# MiCore_LCD.net
KiCad netlist of a schematic drawn in Altium Designer
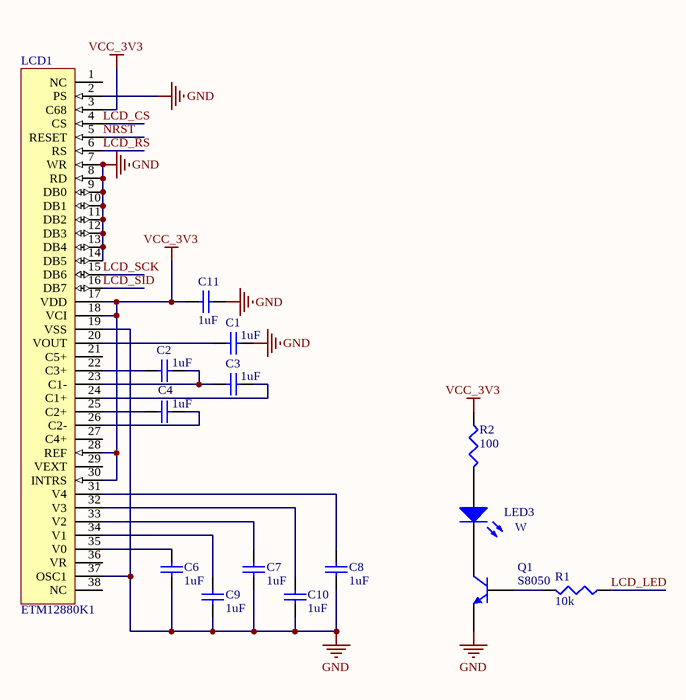
[diagram p0: MiCore_LCD.SchDoc]

(export (version "E")
  (design (tool "Eeschema 10.0.6"))
  (components
    (comp (ref "C1")
      (value "1uF")
      (footprint "0603C")
      (description "Capacitor")
      (fields (field (name "Comment") "Cap") (field (name "PUBLISHER") "Altium Limited"))
      (libsource (lib "Miscellaneous Devices") (part "Cap"))
    )
    (comp (ref "C2")
      (value "1uF")
      (footprint "0603C")
      (description "Capacitor")
      (fields (field (name "Comment") "Cap") (field (name "PUBLISHER") "Altium Limited"))
      (libsource (lib "Miscellaneous Devices") (part "Cap"))
    )
    (comp (ref "C3")
      (value "1uF")
      (footprint "0603C")
      (description "Capacitor")
      (fields (field (name "Comment") "Cap") (field (name "PUBLISHER") "Altium Limited"))
      (libsource (lib "Miscellaneous Devices") (part "Cap"))
    )
    (comp (ref "C4")
      (value "1uF")
      (footprint "0603C")
      (description "Capacitor")
      (fields (field (name "Comment") "Cap") (field (name "PUBLISHER") "Altium Limited"))
      (libsource (lib "Miscellaneous Devices") (part "Cap"))
    )
    (comp (ref "C6")
      (value "1uF")
      (footprint "0603C")
      (description "Capacitor")
      (fields (field (name "Comment") "Cap") (field (name "PUBLISHER") "Altium Limited"))
      (libsource (lib "Miscellaneous Devices") (part "Cap"))
    )
    (comp (ref "C7")
      (value "1uF")
      (footprint "0603C")
      (description "Capacitor")
      (fields (field (name "Comment") "Cap") (field (name "PUBLISHER") "Altium Limited"))
      (libsource (lib "Miscellaneous Devices") (part "Cap"))
    )
    (comp (ref "C8")
      (value "1uF")
      (footprint "0603C")
      (description "Capacitor")
      (fields (field (name "Comment") "Cap") (field (name "PUBLISHER") "Altium Limited"))
      (libsource (lib "Miscellaneous Devices") (part "Cap"))
    )
    (comp (ref "C9")
      (value "1uF")
      (footprint "0603C")
      (description "Capacitor")
      (fields (field (name "Comment") "Cap") (field (name "PUBLISHER") "Altium Limited"))
      (libsource (lib "Miscellaneous Devices") (part "Cap"))
    )
    (comp (ref "C10")
      (value "1uF")
      (footprint "0603C")
      (description "Capacitor")
      (fields (field (name "Comment") "Cap") (field (name "PUBLISHER") "Altium Limited"))
      (libsource (lib "Miscellaneous Devices") (part "Cap"))
    )
    (comp (ref "C11")
      (value "1uF")
      (footprint "0603C")
      (description "Capacitor")
      (fields (field (name "Comment") "Cap") (field (name "PUBLISHER") "Altium Limited"))
      (libsource (lib "Miscellaneous Devices") (part "Cap"))
    )
    (comp (ref "LCD1")
      (value "ETM12880K1")
      (footprint "TL0350_38P")
      (description "LCD, 主控TL0350")
      (libsource (lib "MiCore") (part "ETM12880K1"))
    )
    (comp (ref "LED3")
      (value "W")
      (footprint "1206LED")
      (description "Typical White LED")
      (fields (field (name "PUBLISHER") "Altium Limited"))
      (libsource (lib "Miscellaneous Devices") (part "LED3"))
    )
    (comp (ref "Q1")
      (value "S8050")
      (footprint "SOT-23")
      (description "NPN Bipolar Transistor")
      (fields (field (name "PUBLISHER") "Altium Limited"))
      (libsource (lib "Miscellaneous Devices") (part "NPN"))
    )
    (comp (ref "R1")
      (value "10k")
      (footprint "0603R")
      (description "Resistor")
      (fields (field (name "Comment") "Res3") (field (name "PUBLISHER") "Altium Limited"))
      (libsource (lib "Miscellaneous Devices") (part "Res3"))
    )
    (comp (ref "R2")
      (value "100")
      (footprint "0603R")
      (description "Resistor")
      (fields (field (name "Comment") "Res3") (field (name "PUBLISHER") "Altium Limited"))
      (libsource (lib "Miscellaneous Devices") (part "Res3"))
    )
  )
  (nets
    (net (code "1") (name "/LCD_CS") (class "Default")
      (node (ref "LCD1") (pin "4") (pinfunction "CS_4") (pintype "input"))
    )
    (net (code "2") (name "/LCD_LED") (class "Default")
      (node (ref "R1") (pin "1") (pinfunction "1_1") (pintype "passive"))
    )
    (net (code "3") (name "/LCD_RS") (class "Default")
      (node (ref "LCD1") (pin "6") (pinfunction "RS_6") (pintype "input"))
    )
    (net (code "4") (name "/LCD_SCK") (class "Default")
      (node (ref "LCD1") (pin "15") (pinfunction "DB6_15") (pintype "bidirectional"))
    )
    (net (code "5") (name "/LCD_SID") (class "Default")
      (node (ref "LCD1") (pin "16") (pinfunction "DB7_16") (pintype "bidirectional"))
    )
    (net (code "6") (name "/NRST") (class "Default")
      (node (ref "LCD1") (pin "5") (pinfunction "RESET_5") (pintype "input"))
    )
    (net (code "7") (name "GND") (class "Default")
      (node (ref "C1") (pin "2") (pinfunction "2_2") (pintype "passive"))
      (node (ref "C10") (pin "1") (pinfunction "1_1") (pintype "passive"))
      (node (ref "C11") (pin "2") (pinfunction "2_2") (pintype "passive"))
      (node (ref "C6") (pin "1") (pinfunction "1_1") (pintype "passive"))
      (node (ref "C7") (pin "1") (pinfunction "1_1") (pintype "passive"))
      (node (ref "C8") (pin "1") (pinfunction "1_1") (pintype "passive"))
      (node (ref "C9") (pin "1") (pinfunction "1_1") (pintype "passive"))
      (node (ref "LCD1") (pin "10") (pinfunction "DB1_10") (pintype "bidirectional"))
      (node (ref "LCD1") (pin "11") (pinfunction "DB2_11") (pintype "bidirectional"))
      (node (ref "LCD1") (pin "12") (pinfunction "DB3_12") (pintype "bidirectional"))
      (node (ref "LCD1") (pin "13") (pinfunction "DB4_13") (pintype "bidirectional"))
      (node (ref "LCD1") (pin "14") (pinfunction "DB5_14") (pintype "bidirectional"))
      (node (ref "LCD1") (pin "19") (pinfunction "VSS_19") (pintype "power_in"))
      (node (ref "LCD1") (pin "2") (pinfunction "PS_2") (pintype "input"))
      (node (ref "LCD1") (pin "37") (pinfunction "OSC1_37") (pintype "passive"))
      (node (ref "LCD1") (pin "7") (pinfunction "WR_7") (pintype "input"))
      (node (ref "LCD1") (pin "8") (pinfunction "RD_8") (pintype "input"))
      (node (ref "LCD1") (pin "9") (pinfunction "DB0_9") (pintype "bidirectional"))
      (node (ref "Q1") (pin "3") (pinfunction "E_3") (pintype "passive"))
    )
    (net (code "8") (name "Net-(LCD1-C1+)") (class "Default")
      (node (ref "C3") (pin "2") (pinfunction "2_2") (pintype "passive"))
      (node (ref "LCD1") (pin "24") (pinfunction "C1+_24") (pintype "passive"))
    )
    (net (code "9") (name "Net-(LCD1-C1-)") (class "Default")
      (node (ref "C2") (pin "2") (pinfunction "2_2") (pintype "passive"))
      (node (ref "C3") (pin "1") (pinfunction "1_1") (pintype "passive"))
      (node (ref "LCD1") (pin "23") (pinfunction "C1-_23") (pintype "passive"))
    )
    (net (code "10") (name "Net-(LCD1-C2+)") (class "Default")
      (node (ref "C4") (pin "2") (pinfunction "2_2") (pintype "passive"))
      (node (ref "LCD1") (pin "25") (pinfunction "C2+_25") (pintype "passive"))
    )
    (net (code "11") (name "Net-(LCD1-C2-)") (class "Default")
      (node (ref "C4") (pin "1") (pinfunction "1_1") (pintype "passive"))
      (node (ref "LCD1") (pin "26") (pinfunction "C2-_26") (pintype "passive"))
    )
    (net (code "12") (name "Net-(LCD1-C3+)") (class "Default")
      (node (ref "C2") (pin "1") (pinfunction "1_1") (pintype "passive"))
      (node (ref "LCD1") (pin "22") (pinfunction "C3+_22") (pintype "passive"))
    )
    (net (code "13") (name "Net-(LCD1-V0)") (class "Default")
      (node (ref "C6") (pin "2") (pinfunction "2_2") (pintype "passive"))
      (node (ref "LCD1") (pin "35") (pinfunction "V0_35") (pintype "passive"))
    )
    (net (code "14") (name "Net-(LCD1-V1)") (class "Default")
      (node (ref "C9") (pin "2") (pinfunction "2_2") (pintype "passive"))
      (node (ref "LCD1") (pin "34") (pinfunction "V1_34") (pintype "passive"))
    )
    (net (code "15") (name "Net-(LCD1-V2)") (class "Default")
      (node (ref "C7") (pin "2") (pinfunction "2_2") (pintype "passive"))
      (node (ref "LCD1") (pin "33") (pinfunction "V2_33") (pintype "passive"))
    )
    (net (code "16") (name "Net-(LCD1-V3)") (class "Default")
      (node (ref "C10") (pin "2") (pinfunction "2_2") (pintype "passive"))
      (node (ref "LCD1") (pin "32") (pinfunction "V3_32") (pintype "passive"))
    )
    (net (code "17") (name "Net-(LCD1-V4)") (class "Default")
      (node (ref "C8") (pin "2") (pinfunction "2_2") (pintype "passive"))
      (node (ref "LCD1") (pin "31") (pinfunction "V4_31") (pintype "passive"))
    )
    (net (code "18") (name "Net-(LCD1-VOUT)") (class "Default")
      (node (ref "C1") (pin "1") (pinfunction "1_1") (pintype "passive"))
      (node (ref "LCD1") (pin "20") (pinfunction "VOUT_20") (pintype "passive"))
    )
    (net (code "19") (name "Net-(LED3-A)") (class "Default")
      (node (ref "LED3") (pin "1") (pinfunction "A_1") (pintype "passive"))
      (node (ref "R2") (pin "2") (pinfunction "2_2") (pintype "passive"))
    )
    (net (code "20") (name "Net-(LED3-K)") (class "Default")
      (node (ref "LED3") (pin "2") (pinfunction "K_2") (pintype "passive"))
      (node (ref "Q1") (pin "1") (pinfunction "C_1") (pintype "passive"))
    )
    (net (code "21") (name "Net-(Q1-B)") (class "Default")
      (node (ref "Q1") (pin "2") (pinfunction "B_2") (pintype "passive"))
      (node (ref "R1") (pin "2") (pinfunction "2_2") (pintype "passive"))
    )
    (net (code "22") (name "VCC_3V3") (class "Default")
      (node (ref "C11") (pin "1") (pinfunction "1_1") (pintype "passive"))
      (node (ref "LCD1") (pin "17") (pinfunction "VDD_17") (pintype "power_in"))
      (node (ref "LCD1") (pin "18") (pinfunction "VCI_18") (pintype "power_in"))
      (node (ref "LCD1") (pin "28") (pinfunction "REF_28") (pintype "input"))
      (node (ref "LCD1") (pin "3") (pinfunction "C68_3") (pintype "input"))
      (node (ref "LCD1") (pin "30") (pinfunction "INTRS_30") (pintype "input"))
      (node (ref "R2") (pin "1") (pinfunction "1_1") (pintype "passive"))
    )
    (net (code "23") (name "unconnected-(LCD1-C4+-Pad27)") (class "Default")
      (node (ref "LCD1") (pin "27") (pinfunction "C4+_27") (pintype "passive"))
    )
    (net (code "24") (name "unconnected-(LCD1-C5+-Pad21)") (class "Default")
      (node (ref "LCD1") (pin "21") (pinfunction "C5+_21") (pintype "passive"))
    )
    (net (code "25") (name "unconnected-(LCD1-NC-Pad1)") (class "Default")
      (node (ref "LCD1") (pin "1") (pinfunction "NC_1") (pintype "tri_state"))
    )
    (net (code "26") (name "unconnected-(LCD1-NC-Pad38)") (class "Default")
      (node (ref "LCD1") (pin "38") (pinfunction "NC_38") (pintype "tri_state"))
    )
    (net (code "27") (name "unconnected-(LCD1-VEXT-Pad29)") (class "Default")
      (node (ref "LCD1") (pin "29") (pinfunction "VEXT_29") (pintype "passive"))
    )
    (net (code "28") (name "unconnected-(LCD1-VR-Pad36)") (class "Default")
      (node (ref "LCD1") (pin "36") (pinfunction "VR_36") (pintype "passive"))
    )
  )
)
